# BC127.net
KiCad netlist of a schematic drawn in Altium Designer
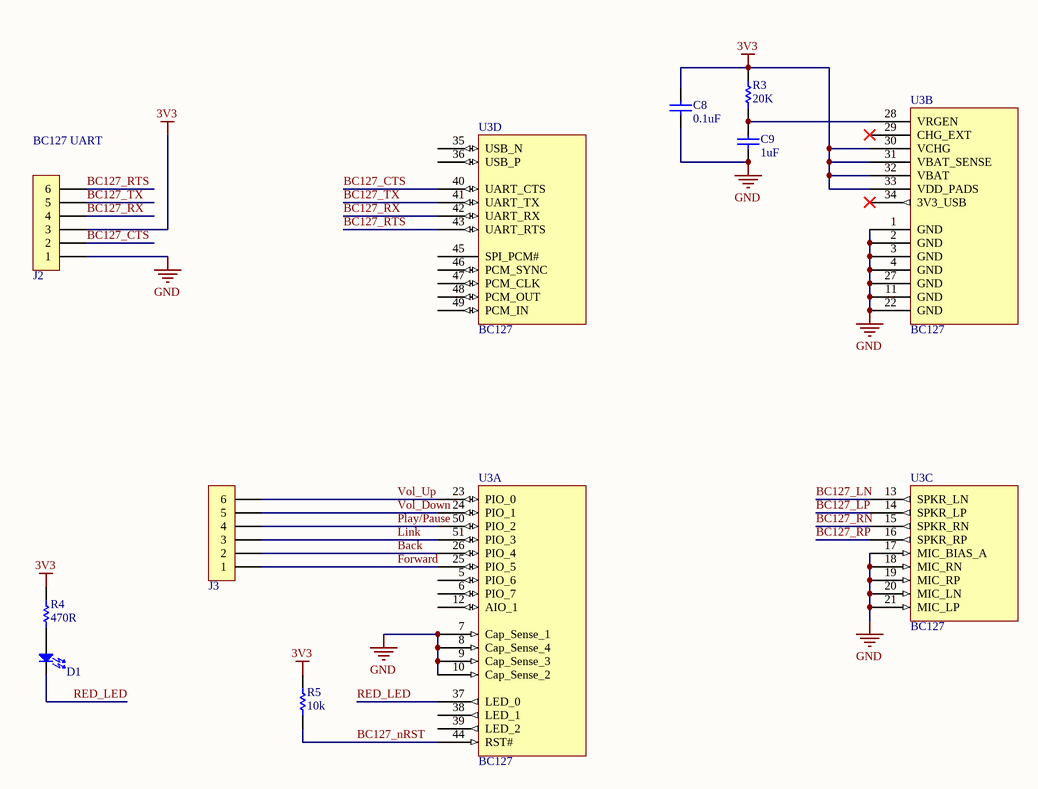
[diagram p0: BC127.SchDoc]

(export (version "E")
  (design (tool "Eeschema 10.0.6"))
  (components
    (comp (ref "C8")
      (value "0.1uF")
      (footprint "CAPC1608X09N")
      (fields
        (field (name "DIGIKEY PART NUMBER") "490-1519-1-ND")
        (field (name "VOLTAGE") "50V")
        (field (name "TOLERANCE") "10%")
      )
      (libsource (lib "Speaker Library") (part "CAP CER 0.1uF 0603"))
    )
    (comp (ref "C9")
      (value "1uF")
      (footprint "CAPC1608X09N")
      (fields
        (field (name "DIGIKEY PART NUMBER") "490-10487-1-ND")
        (field (name "VOLTAGE") "35V")
        (field (name "MANUFACTURER") "Murata")
      )
      (libsource (lib "Speaker Library") (part "CAP CER 1uF 0603"))
    )
    (comp (ref "D1")
      (value "LED 0603")
      (footprint "DIOM1608X08N")
      (fields (field (name "VOLTAGE") "2.2V") (field (name "DIGIKEY PART NUMBER") "160-1447-1-ND"))
      (libsource (lib "Speaker Library") (part "LED 0603"))
    )
    (comp (ref "J2")
      (value "6POS THRU HOLE 2.0MM")
      (footprint "JST PH-6")
      (fields (field (name "DIGIKEY PART NUMBER") "455-1708-ND"))
      (libsource (lib "Speaker Library") (part "6POS THRU HOLE 2.0MM"))
    )
    (comp (ref "J3")
      (value "6POS THRU HOLE 2.0MM")
      (footprint "JST PH-6")
      (fields (field (name "DIGIKEY PART NUMBER") "455-1708-ND"))
      (libsource (lib "Speaker Library") (part "6POS THRU HOLE 2.0MM"))
    )
    (comp (ref "R3")
      (value "20K")
      (footprint "RESC1608X06N")
      (fields
        (field (name "TOLERANCE") "1%")
        (field (name "POWER") "0.1W")
        (field (name "DIGIKEY PART NUMBER") "311-20.0KHRCT-ND")
      )
      (libsource (lib "Speaker Library") (part "RES 20K 0603"))
    )
    (comp (ref "R4")
      (value "470R")
      (footprint "RESC1608X06N")
      (fields
        (field (name "TOLERANCE") "1%")
        (field (name "POWER") "0.25W")
        (field (name "DIGIKEY PART NUMBER") "311-470HRCT-ND")
      )
      (libsource (lib "Speaker Library") (part "RES 470R 0603"))
    )
    (comp (ref "R5")
      (value "10k")
      (footprint "RESC1608X06N")
      (fields
        (field (name "TOLERANCE") "1%")
        (field (name "POWER") "0.1W")
        (field (name "MANUFACTURER") "Yageo")
      )
      (libsource (lib "Speaker Library") (part "RES 10K 0603"))
    )
    (comp (ref "U3") (value "BC127") (footprint "BC127") (libsource (lib "Speaker Library") (part "BC127")))
  )
  (nets
    (net (code "1") (name "/BC127_CTS") (class "Default")
      (node (ref "J2") (pin "2") (pinfunction "2_2") (pintype "passive"))
      (node (ref "U3") (pin "40") (pinfunction "UART_CTS_40") (pintype "bidirectional"))
    )
    (net (code "2") (name "/BC127_LN") (class "Default")
      (node (ref "U3") (pin "13") (pinfunction "SPKR_LN_13") (pintype "output"))
    )
    (net (code "3") (name "/BC127_LP") (class "Default")
      (node (ref "U3") (pin "14") (pinfunction "SPKR_LP_14") (pintype "output"))
    )
    (net (code "4") (name "/BC127_RN") (class "Default")
      (node (ref "U3") (pin "15") (pinfunction "SPKR_RN_15") (pintype "output"))
    )
    (net (code "5") (name "/BC127_RP") (class "Default")
      (node (ref "U3") (pin "16") (pinfunction "SPKR_RP_16") (pintype "output"))
    )
    (net (code "6") (name "/BC127_RTS") (class "Default")
      (node (ref "J2") (pin "6") (pinfunction "6_6") (pintype "passive"))
      (node (ref "U3") (pin "43") (pinfunction "UART_RTS_43") (pintype "bidirectional"))
    )
    (net (code "7") (name "/BC127_RX") (class "Default")
      (node (ref "J2") (pin "4") (pinfunction "4_4") (pintype "passive"))
      (node (ref "U3") (pin "42") (pinfunction "UART_RX_42") (pintype "bidirectional"))
    )
    (net (code "8") (name "/BC127_TX") (class "Default")
      (node (ref "J2") (pin "5") (pinfunction "5_5") (pintype "passive"))
      (node (ref "U3") (pin "41") (pinfunction "UART_TX_41") (pintype "bidirectional"))
    )
    (net (code "9") (name "/BC127_nRST") (class "Default")
      (node (ref "R5") (pin "1") (pinfunction "1_1") (pintype "passive"))
      (node (ref "U3") (pin "44") (pinfunction "RST#_44") (pintype "input"))
    )
    (net (code "10") (name "/Back") (class "Default")
      (node (ref "J3") (pin "2") (pinfunction "2_2") (pintype "passive"))
      (node (ref "U3") (pin "26") (pinfunction "PIO_4_26") (pintype "bidirectional"))
    )
    (net (code "11") (name "/Forward") (class "Default")
      (node (ref "J3") (pin "1") (pinfunction "1_1") (pintype "passive"))
      (node (ref "U3") (pin "25") (pinfunction "PIO_5_25") (pintype "bidirectional"))
    )
    (net (code "12") (name "/Link") (class "Default")
      (node (ref "J3") (pin "3") (pinfunction "3_3") (pintype "passive"))
      (node (ref "U3") (pin "51") (pinfunction "PIO_3_51") (pintype "bidirectional"))
    )
    (net (code "13") (name "/Play{slash}Pause") (class "Default")
      (node (ref "J3") (pin "4") (pinfunction "4_4") (pintype "passive"))
      (node (ref "U3") (pin "50") (pinfunction "PIO_2_50") (pintype "bidirectional"))
    )
    (net (code "14") (name "/RED_LED") (class "Default")
      (node (ref "D1") (pin "1") (pinfunction "K2_1") (pintype "passive"))
      (node (ref "U3") (pin "37") (pinfunction "LED_0_37") (pintype "output"))
    )
    (net (code "15") (name "/Vol_Down") (class "Default")
      (node (ref "J3") (pin "5") (pinfunction "5_5") (pintype "passive"))
      (node (ref "U3") (pin "24") (pinfunction "PIO_1_24") (pintype "bidirectional"))
    )
    (net (code "16") (name "/Vol_Up") (class "Default")
      (node (ref "J3") (pin "6") (pinfunction "6_6") (pintype "passive"))
      (node (ref "U3") (pin "23") (pinfunction "PIO_0_23") (pintype "bidirectional"))
    )
    (net (code "17") (name "3V3") (class "Default")
      (node (ref "C8") (pin "2") (pinfunction "2_2") (pintype "passive"))
      (node (ref "J2") (pin "3") (pinfunction "3_3") (pintype "passive"))
      (node (ref "R3") (pin "2") (pinfunction "2_2") (pintype "passive"))
      (node (ref "R4") (pin "2") (pinfunction "2_2") (pintype "passive"))
      (node (ref "R5") (pin "2") (pinfunction "2_2") (pintype "passive"))
      (node (ref "U3") (pin "30") (pinfunction "VCHG_30") (pintype "passive"))
      (node (ref "U3") (pin "31") (pinfunction "VBAT_SENSE_31") (pintype "passive"))
      (node (ref "U3") (pin "32") (pinfunction "VBAT_32") (pintype "passive"))
      (node (ref "U3") (pin "33") (pinfunction "VDD_PADS_33") (pintype "power_in"))
    )
    (net (code "18") (name "GND") (class "Default")
      (node (ref "C8") (pin "1") (pinfunction "1_1") (pintype "passive"))
      (node (ref "C9") (pin "1") (pinfunction "1_1") (pintype "passive"))
      (node (ref "J2") (pin "1") (pinfunction "1_1") (pintype "passive"))
      (node (ref "U3") (pin "1") (pinfunction "GND_1") (pintype "power_in"))
      (node (ref "U3") (pin "10") (pinfunction "Cap_Sense_2_10") (pintype "input"))
      (node (ref "U3") (pin "11") (pinfunction "GND_11") (pintype "power_in"))
      (node (ref "U3") (pin "17") (pinfunction "MIC_BIAS_A_17") (pintype "input"))
      (node (ref "U3") (pin "18") (pinfunction "MIC_RN_18") (pintype "input"))
      (node (ref "U3") (pin "19") (pinfunction "MIC_RP_19") (pintype "input"))
      (node (ref "U3") (pin "2") (pinfunction "GND_2") (pintype "power_in"))
      (node (ref "U3") (pin "20") (pinfunction "MIC_LN_20") (pintype "input"))
      (node (ref "U3") (pin "21") (pinfunction "MIC_LP_21") (pintype "input"))
      (node (ref "U3") (pin "22") (pinfunction "GND_22") (pintype "power_in"))
      (node (ref "U3") (pin "27") (pinfunction "GND_27") (pintype "power_in"))
      (node (ref "U3") (pin "3") (pinfunction "GND_3") (pintype "power_in"))
      (node (ref "U3") (pin "4") (pinfunction "GND_4") (pintype "power_in"))
      (node (ref "U3") (pin "7") (pinfunction "Cap_Sense_1_7") (pintype "input"))
      (node (ref "U3") (pin "8") (pinfunction "Cap_Sense_4_8") (pintype "input"))
      (node (ref "U3") (pin "9") (pinfunction "Cap_Sense_3_9") (pintype "input"))
    )
    (net (code "19") (name "Net-(D1-A2)") (class "Default")
      (node (ref "D1") (pin "2") (pinfunction "A2_2") (pintype "passive"))
      (node (ref "R4") (pin "1") (pinfunction "1_1") (pintype "passive"))
    )
    (net (code "20") (name "Net-(U3B-VRGEN)") (class "Default")
      (node (ref "C9") (pin "2") (pinfunction "2_2") (pintype "passive"))
      (node (ref "R3") (pin "1") (pinfunction "1_1") (pintype "passive"))
      (node (ref "U3") (pin "28") (pinfunction "VRGEN_28") (pintype "passive"))
    )
    (net (code "21") (name "unconnected-(U3A-AIO_1-Pad12)") (class "Default")
      (node (ref "U3") (pin "12") (pinfunction "AIO_1_12") (pintype "bidirectional"))
    )
    (net (code "22") (name "unconnected-(U3A-LED_1-Pad38)") (class "Default")
      (node (ref "U3") (pin "38") (pinfunction "LED_1_38") (pintype "output"))
    )
    (net (code "23") (name "unconnected-(U3A-LED_2-Pad39)") (class "Default")
      (node (ref "U3") (pin "39") (pinfunction "LED_2_39") (pintype "output"))
    )
    (net (code "24") (name "unconnected-(U3A-PIO_6-Pad5)") (class "Default")
      (node (ref "U3") (pin "5") (pinfunction "PIO_6_5") (pintype "bidirectional"))
    )
    (net (code "25") (name "unconnected-(U3A-PIO_7-Pad6)") (class "Default")
      (node (ref "U3") (pin "6") (pinfunction "PIO_7_6") (pintype "bidirectional"))
    )
    (net (code "26") (name "unconnected-(U3B-3V3_USB-Pad34)") (class "Default")
      (node (ref "U3") (pin "34") (pinfunction "3V3_USB_34") (pintype "output+no_connect"))
    )
    (net (code "27") (name "unconnected-(U3B-CHG_EXT-Pad29)") (class "Default")
      (node (ref "U3") (pin "29") (pinfunction "CHG_EXT_29") (pintype "passive+no_connect"))
    )
    (net (code "28") (name "unconnected-(U3D-PCM_CLK-Pad47)") (class "Default")
      (node (ref "U3") (pin "47") (pinfunction "PCM_CLK_47") (pintype "bidirectional"))
    )
    (net (code "29") (name "unconnected-(U3D-PCM_IN-Pad49)") (class "Default")
      (node (ref "U3") (pin "49") (pinfunction "PCM_IN_49") (pintype "bidirectional"))
    )
    (net (code "30") (name "unconnected-(U3D-PCM_OUT-Pad48)") (class "Default")
      (node (ref "U3") (pin "48") (pinfunction "PCM_OUT_48") (pintype "bidirectional"))
    )
    (net (code "31") (name "unconnected-(U3D-PCM_SYNC-Pad46)") (class "Default")
      (node (ref "U3") (pin "46") (pinfunction "PCM_SYNC_46") (pintype "bidirectional"))
    )
    (net (code "32") (name "unconnected-(U3D-SPI_PCM#-Pad45)") (class "Default")
      (node (ref "U3") (pin "45") (pinfunction "SPI_PCM#_45") (pintype "passive"))
    )
    (net (code "33") (name "unconnected-(U3D-USB_N-Pad35)") (class "Default")
      (node (ref "U3") (pin "35") (pinfunction "USB_N_35") (pintype "bidirectional"))
    )
    (net (code "34") (name "unconnected-(U3D-USB_P-Pad36)") (class "Default")
      (node (ref "U3") (pin "36") (pinfunction "USB_P_36") (pintype "bidirectional"))
    )
  )
)
